# SCH_3-14-Pi-day-PCB_2024-06-02.net
KiCad netlist of a schematic drawn in EasyEDA
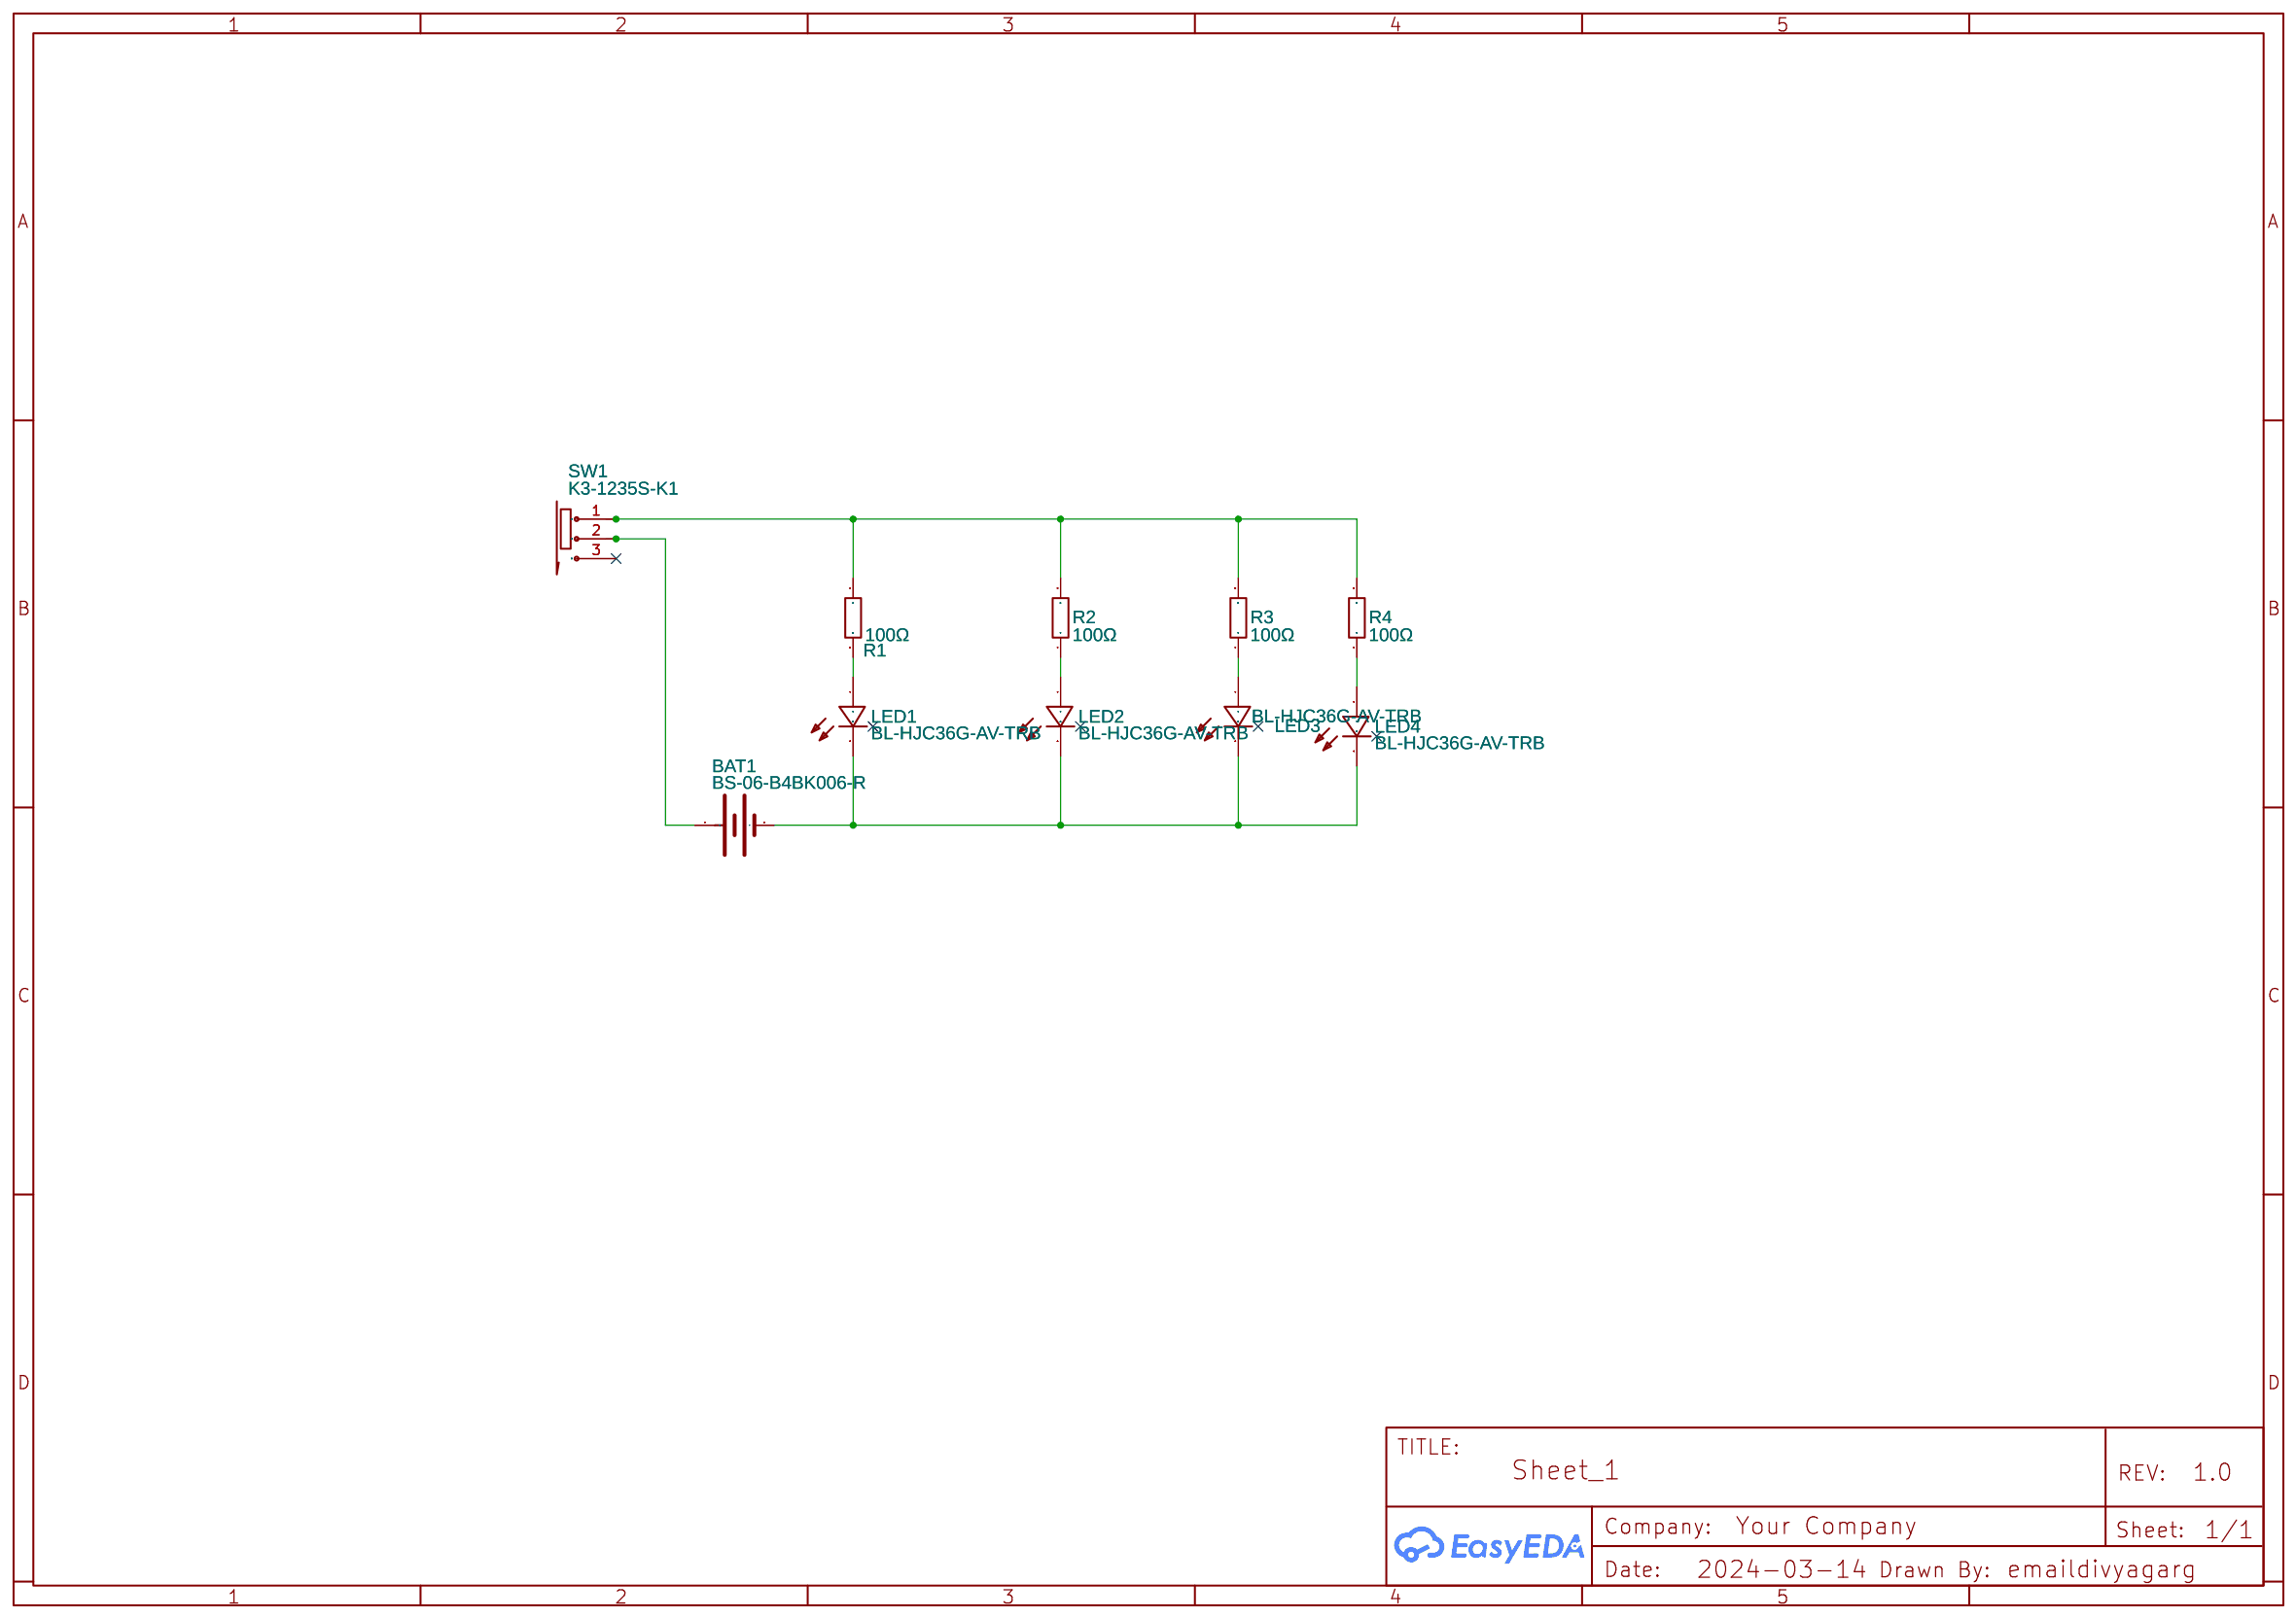
[diagram p0: schematic sheet]

(export (version "E")
  (design (tool "Eeschema 10.0.6"))
  (components
    (comp (ref "BAT1")
      (value "BS-06-B4BK006-R")
      (fields (field (name "Manufacturer") "MYOUNG(美阳)"))
      (libsource (lib "") (part "BS-06-B4BK006-R"))
    )
    (comp (ref "LED1")
      (value "BL-HJC36G-AV-TRB")
      (fields (field (name "Manufacturer") "BrtLed(佰鸿)"))
      (libsource (lib "") (part "BL-HJC36G-AV-TRB"))
    )
    (comp (ref "LED2")
      (value "BL-HJC36G-AV-TRB")
      (fields (field (name "Manufacturer") "BrtLed(佰鸿)"))
      (libsource (lib "") (part "BL-HJC36G-AV-TRB"))
    )
    (comp (ref "LED3")
      (value "BL-HJC36G-AV-TRB")
      (fields (field (name "Manufacturer") "BrtLed(佰鸿)"))
      (libsource (lib "") (part "BL-HJC36G-AV-TRB"))
    )
    (comp (ref "LED4")
      (value "BL-HJC36G-AV-TRB")
      (fields (field (name "Manufacturer") "BrtLed(佰鸿)"))
      (libsource (lib "") (part "BL-HJC36G-AV-TRB"))
    )
    (comp (ref "R1")
      (value "100Ω")
      (fields
        (field (name "Manufacturer Part") "25121WF1000T4E")
        (field (name "Manufacturer") "UNI-ROYAL(厚声)")
      )
      (libsource (lib "") (part "25121WF1000T4E_1"))
    )
    (comp (ref "R2")
      (value "100Ω")
      (fields
        (field (name "Manufacturer Part") "25121WF1000T4E")
        (field (name "Manufacturer") "UNI-ROYAL(厚声)")
      )
      (libsource (lib "") (part "25121WF1000T4E"))
    )
    (comp (ref "R3")
      (value "100Ω")
      (fields
        (field (name "Manufacturer Part") "25121WF1000T4E")
        (field (name "Manufacturer") "UNI-ROYAL(厚声)")
      )
      (libsource (lib "") (part "25121WF1000T4E"))
    )
    (comp (ref "R4")
      (value "100Ω")
      (fields
        (field (name "Manufacturer Part") "25121WF1000T4E")
        (field (name "Manufacturer") "UNI-ROYAL(厚声)")
      )
      (libsource (lib "") (part "25121WF1000T4E"))
    )
    (comp (ref "SW1")
      (value "K3-1235S-K1")
      (fields (field (name "Manufacturer") "韩国韩荣"))
      (libsource (lib "") (part "K3-1235S-K1"))
    )
  )
  (nets
    (net (code "1") (name "Net-(BAT1-+)") (class "Default")
      (node (ref "BAT1") (pin "1") (pinfunction "+_1") (pintype "passive"))
      (node (ref "SW1") (pin "2") (pinfunction "2_2") (pintype "unspecified"))
    )
    (net (code "2") (name "Net-(BAT1--)") (class "Default")
      (node (ref "BAT1") (pin "2") (pinfunction "-_2") (pintype "passive"))
      (node (ref "LED1") (pin "2") (pinfunction "C_2") (pintype "unspecified"))
      (node (ref "LED2") (pin "2") (pinfunction "C_2") (pintype "unspecified"))
      (node (ref "LED3") (pin "2") (pinfunction "C_2") (pintype "unspecified"))
      (node (ref "LED4") (pin "2") (pinfunction "C_2") (pintype "unspecified"))
    )
    (net (code "3") (name "Net-(LED1-A)") (class "Default")
      (node (ref "LED1") (pin "1") (pinfunction "A_1") (pintype "unspecified"))
      (node (ref "R1") (pin "2") (pinfunction "2_2") (pintype "input"))
    )
    (net (code "4") (name "Net-(LED2-A)") (class "Default")
      (node (ref "LED2") (pin "1") (pinfunction "A_1") (pintype "unspecified"))
      (node (ref "R2") (pin "1") (pinfunction "1_1") (pintype "input"))
    )
    (net (code "5") (name "Net-(LED3-A)") (class "Default")
      (node (ref "LED3") (pin "1") (pinfunction "A_1") (pintype "unspecified"))
      (node (ref "R3") (pin "1") (pinfunction "1_1") (pintype "input"))
    )
    (net (code "6") (name "Net-(LED4-A)") (class "Default")
      (node (ref "LED4") (pin "1") (pinfunction "A_1") (pintype "unspecified"))
      (node (ref "R4") (pin "1") (pinfunction "1_1") (pintype "input"))
    )
    (net (code "7") (name "Net-(R1-Pad1)") (class "Default")
      (node (ref "R1") (pin "1") (pinfunction "1_1") (pintype "input"))
      (node (ref "R2") (pin "2") (pinfunction "2_2") (pintype "input"))
      (node (ref "R3") (pin "2") (pinfunction "2_2") (pintype "input"))
      (node (ref "R4") (pin "2") (pinfunction "2_2") (pintype "input"))
      (node (ref "SW1") (pin "1") (pinfunction "1_1") (pintype "unspecified"))
    )
    (net (code "8") (name "unconnected-(SW1-Pad3)") (class "Default")
      (node (ref "SW1") (pin "3") (pinfunction "3_3") (pintype "unspecified+no_connect"))
    )
  )
)
